# SCH_NFC-Card_2024-10-11.net
KiCad netlist of a schematic drawn in EasyEDA
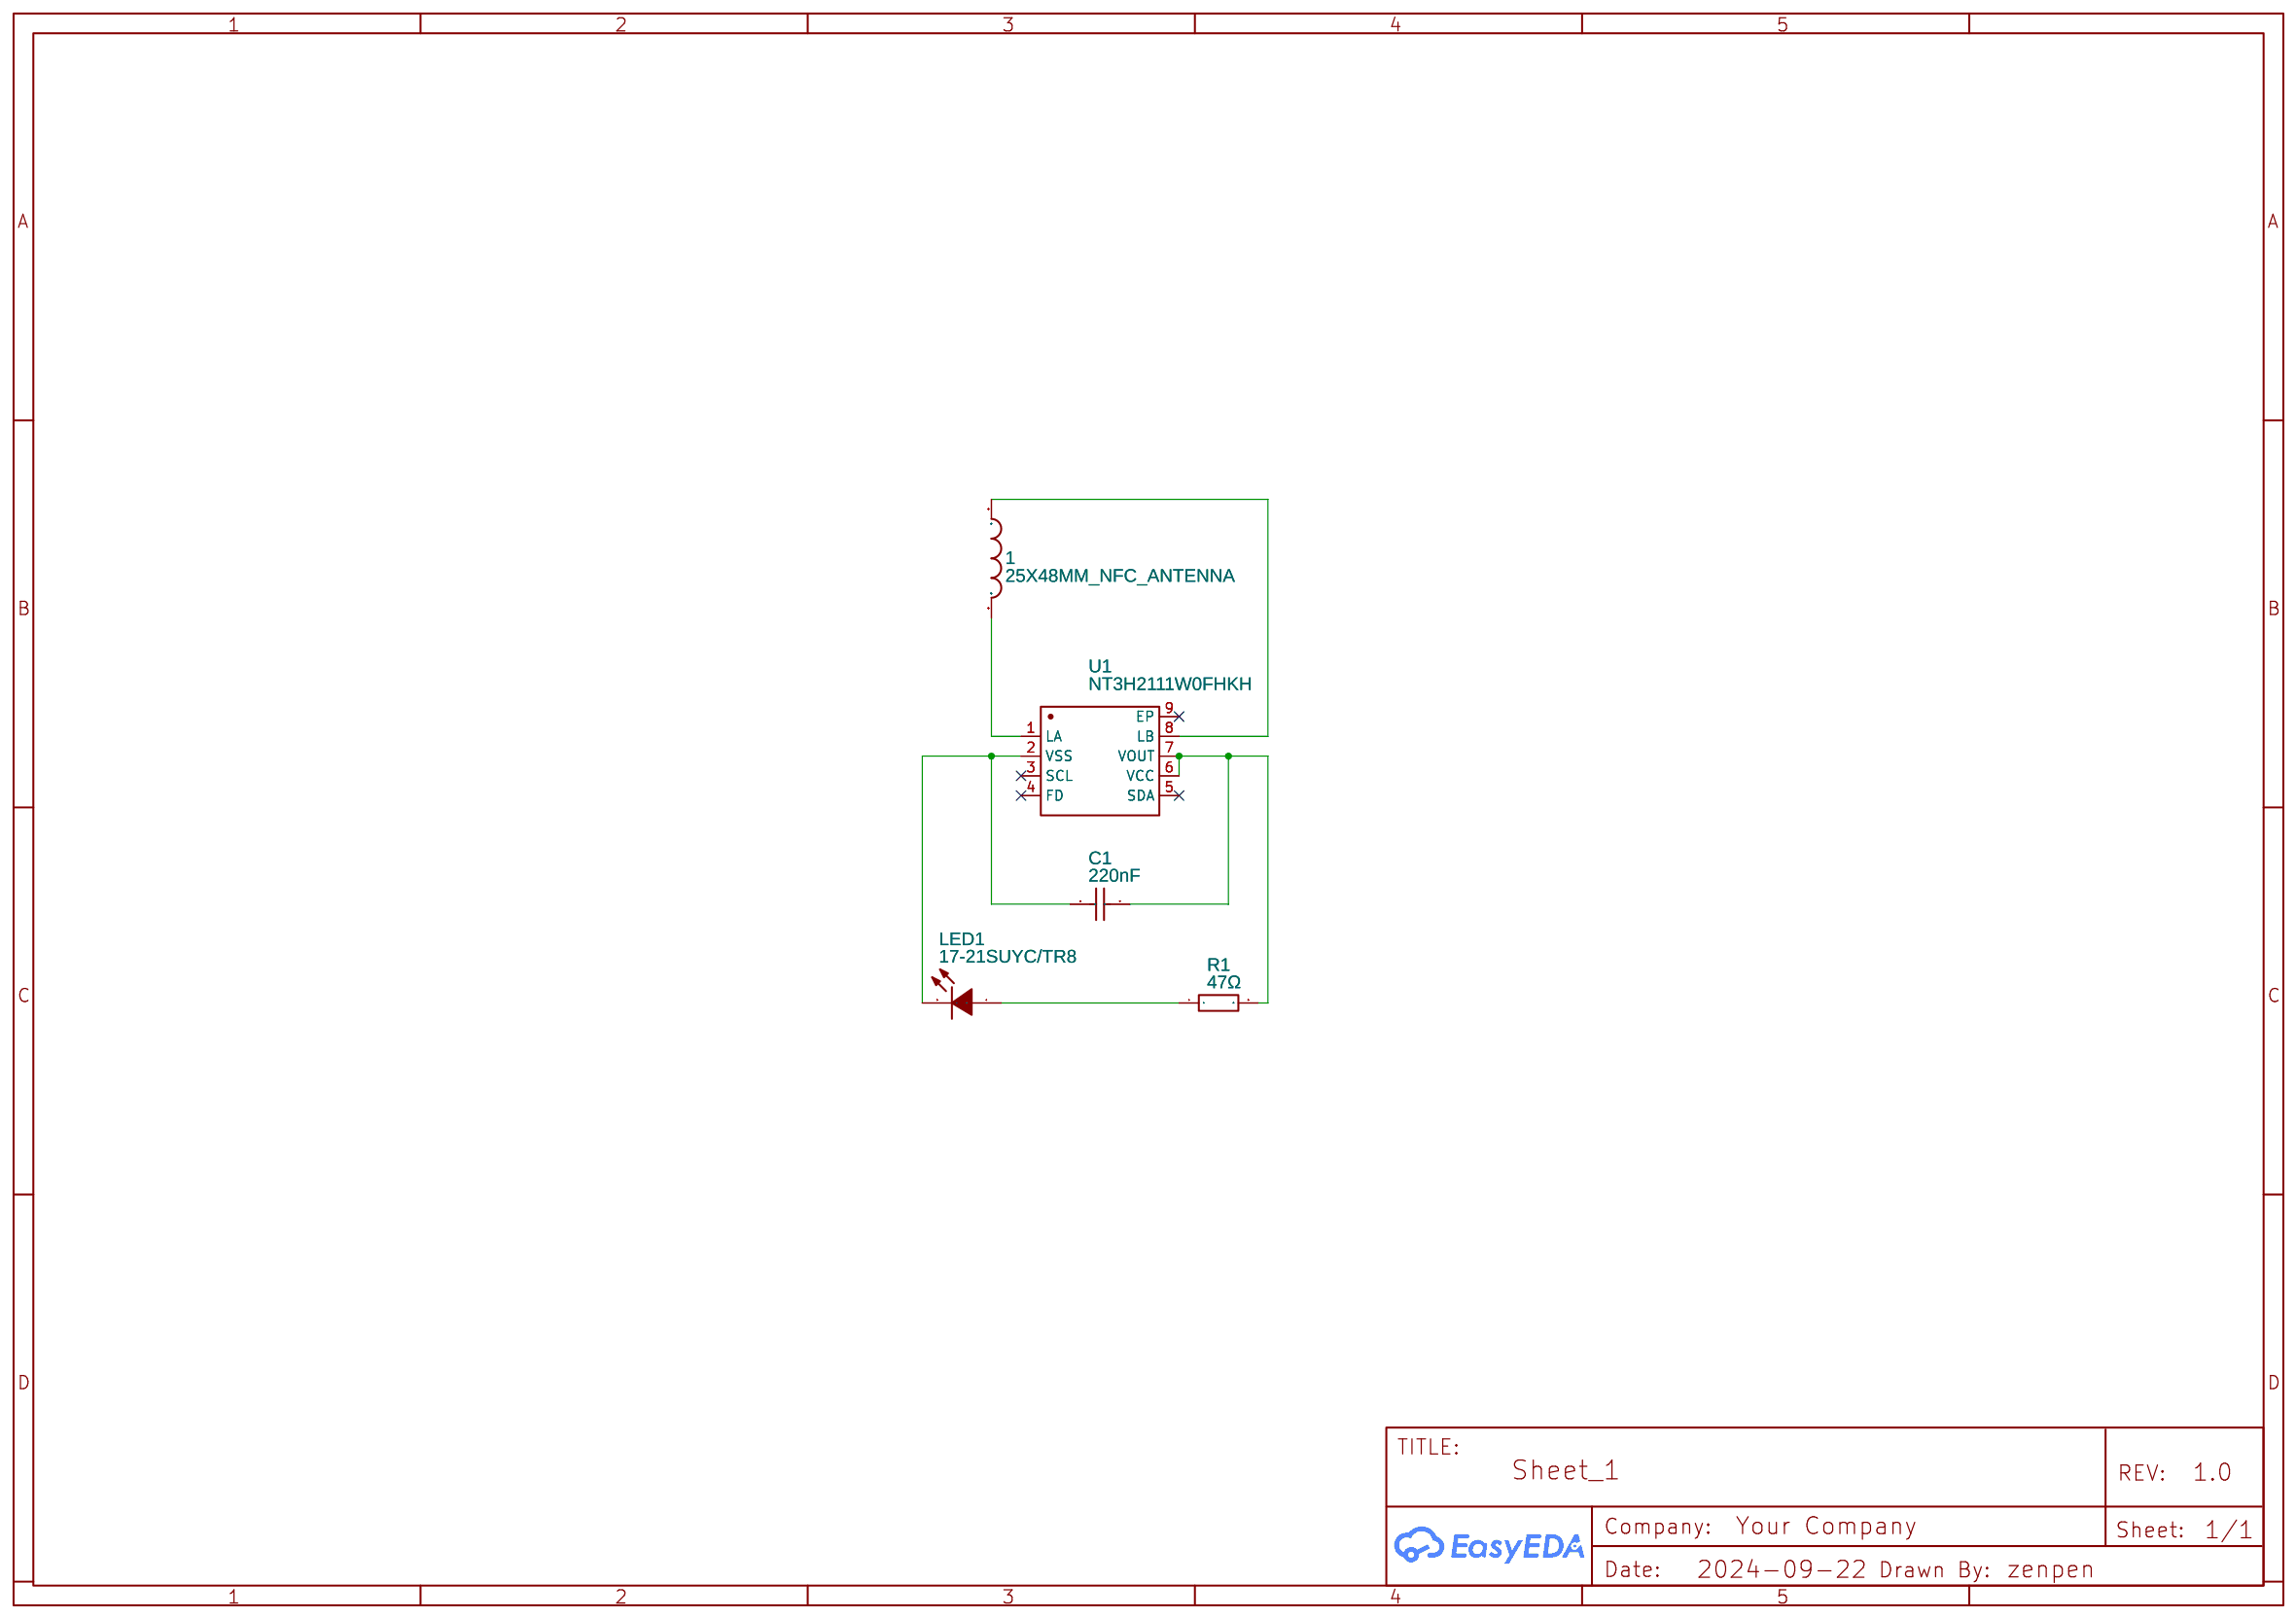
[diagram p0: schematic sheet]

(export (version "E")
  (design (tool "Eeschema 10.0.6"))
  (components
    (comp (ref "1") (value "25X48MM_NFC_ANTENNA") (libsource (lib "") (part "25X48MM_NFC_ANTENNA")))
    (comp (ref "C1")
      (value "220nF")
      (fields
        (field (name "Manufacturer Part") "CL10B224KA8NNNC")
        (field (name "Manufacturer") "SAMSUNG(三星)")
      )
      (libsource (lib "") (part "CL10B224KA8NNNC"))
    )
    (comp (ref "LED1")
      (value "17-21SUYC/TR8")
      (fields (field (name "Manufacturer Part") "KT-0805黄灯") (field (name "Manufacturer") "KENTO"))
      (libsource (lib "") (part "17-21SUYC/TR8"))
    )
    (comp (ref "R1")
      (value "47Ω")
      (fields
        (field (name "Manufacturer Part") "0603WAF470JT5E")
        (field (name "Manufacturer") "UNI-ROYAL(厚声)")
      )
      (libsource (lib "") (part "0603WAF470JT5E"))
    )
    (comp (ref "U1")
      (value "NT3H2111W0FHKH")
      (fields (field (name "Manufacturer") "NXP(恩智浦)"))
      (libsource (lib "") (part "NT3H2111W0FHKH"))
    )
  )
  (nets
    (net (code "1") (name "Net-(LED1-+)") (class "Default")
      (node (ref "LED1") (pin "1") (pinfunction "+_1") (pintype "unspecified"))
      (node (ref "R1") (pin "1") (pinfunction "1_1") (pintype "input"))
    )
    (net (code "2") (name "Net-(LED1--)") (class "Default")
      (node (ref "C1") (pin "1") (pinfunction "1_1") (pintype "input"))
      (node (ref "LED1") (pin "2") (pinfunction "-_2") (pintype "unspecified"))
      (node (ref "U1") (pin "2") (pinfunction "VSS_2") (pintype "unspecified"))
    )
    (net (code "3") (name "Net-(U1-LA)") (class "Default")
      (node (ref "1") (pin "P$2") (pinfunction "P$2_P$2") (pintype "bidirectional"))
      (node (ref "U1") (pin "1") (pinfunction "LA_1") (pintype "unspecified"))
    )
    (net (code "4") (name "Net-(U1-LB)") (class "Default")
      (node (ref "1") (pin "P$1") (pinfunction "P$1_P$1") (pintype "bidirectional"))
      (node (ref "U1") (pin "8") (pinfunction "LB_8") (pintype "unspecified"))
    )
    (net (code "5") (name "Net-(U1-VCC)") (class "Default")
      (node (ref "C1") (pin "2") (pinfunction "2_2") (pintype "input"))
      (node (ref "R1") (pin "2") (pinfunction "2_2") (pintype "input"))
      (node (ref "U1") (pin "6") (pinfunction "VCC_6") (pintype "unspecified"))
      (node (ref "U1") (pin "7") (pinfunction "VOUT_7") (pintype "unspecified"))
    )
    (net (code "6") (name "unconnected-(U1-EP-Pad9)") (class "Default")
      (node (ref "U1") (pin "9") (pinfunction "EP_9") (pintype "unspecified+no_connect"))
    )
    (net (code "7") (name "unconnected-(U1-FD-Pad4)") (class "Default")
      (node (ref "U1") (pin "4") (pinfunction "FD_4") (pintype "unspecified+no_connect"))
    )
    (net (code "8") (name "unconnected-(U1-SCL-Pad3)") (class "Default")
      (node (ref "U1") (pin "3") (pinfunction "SCL_3") (pintype "unspecified+no_connect"))
    )
    (net (code "9") (name "unconnected-(U1-SDA-Pad5)") (class "Default")
      (node (ref "U1") (pin "5") (pinfunction "SDA_5") (pintype "unspecified+no_connect"))
    )
  )
)
